# signal_processing_module.net
KiCad netlist of a schematic drawn in EAGLE
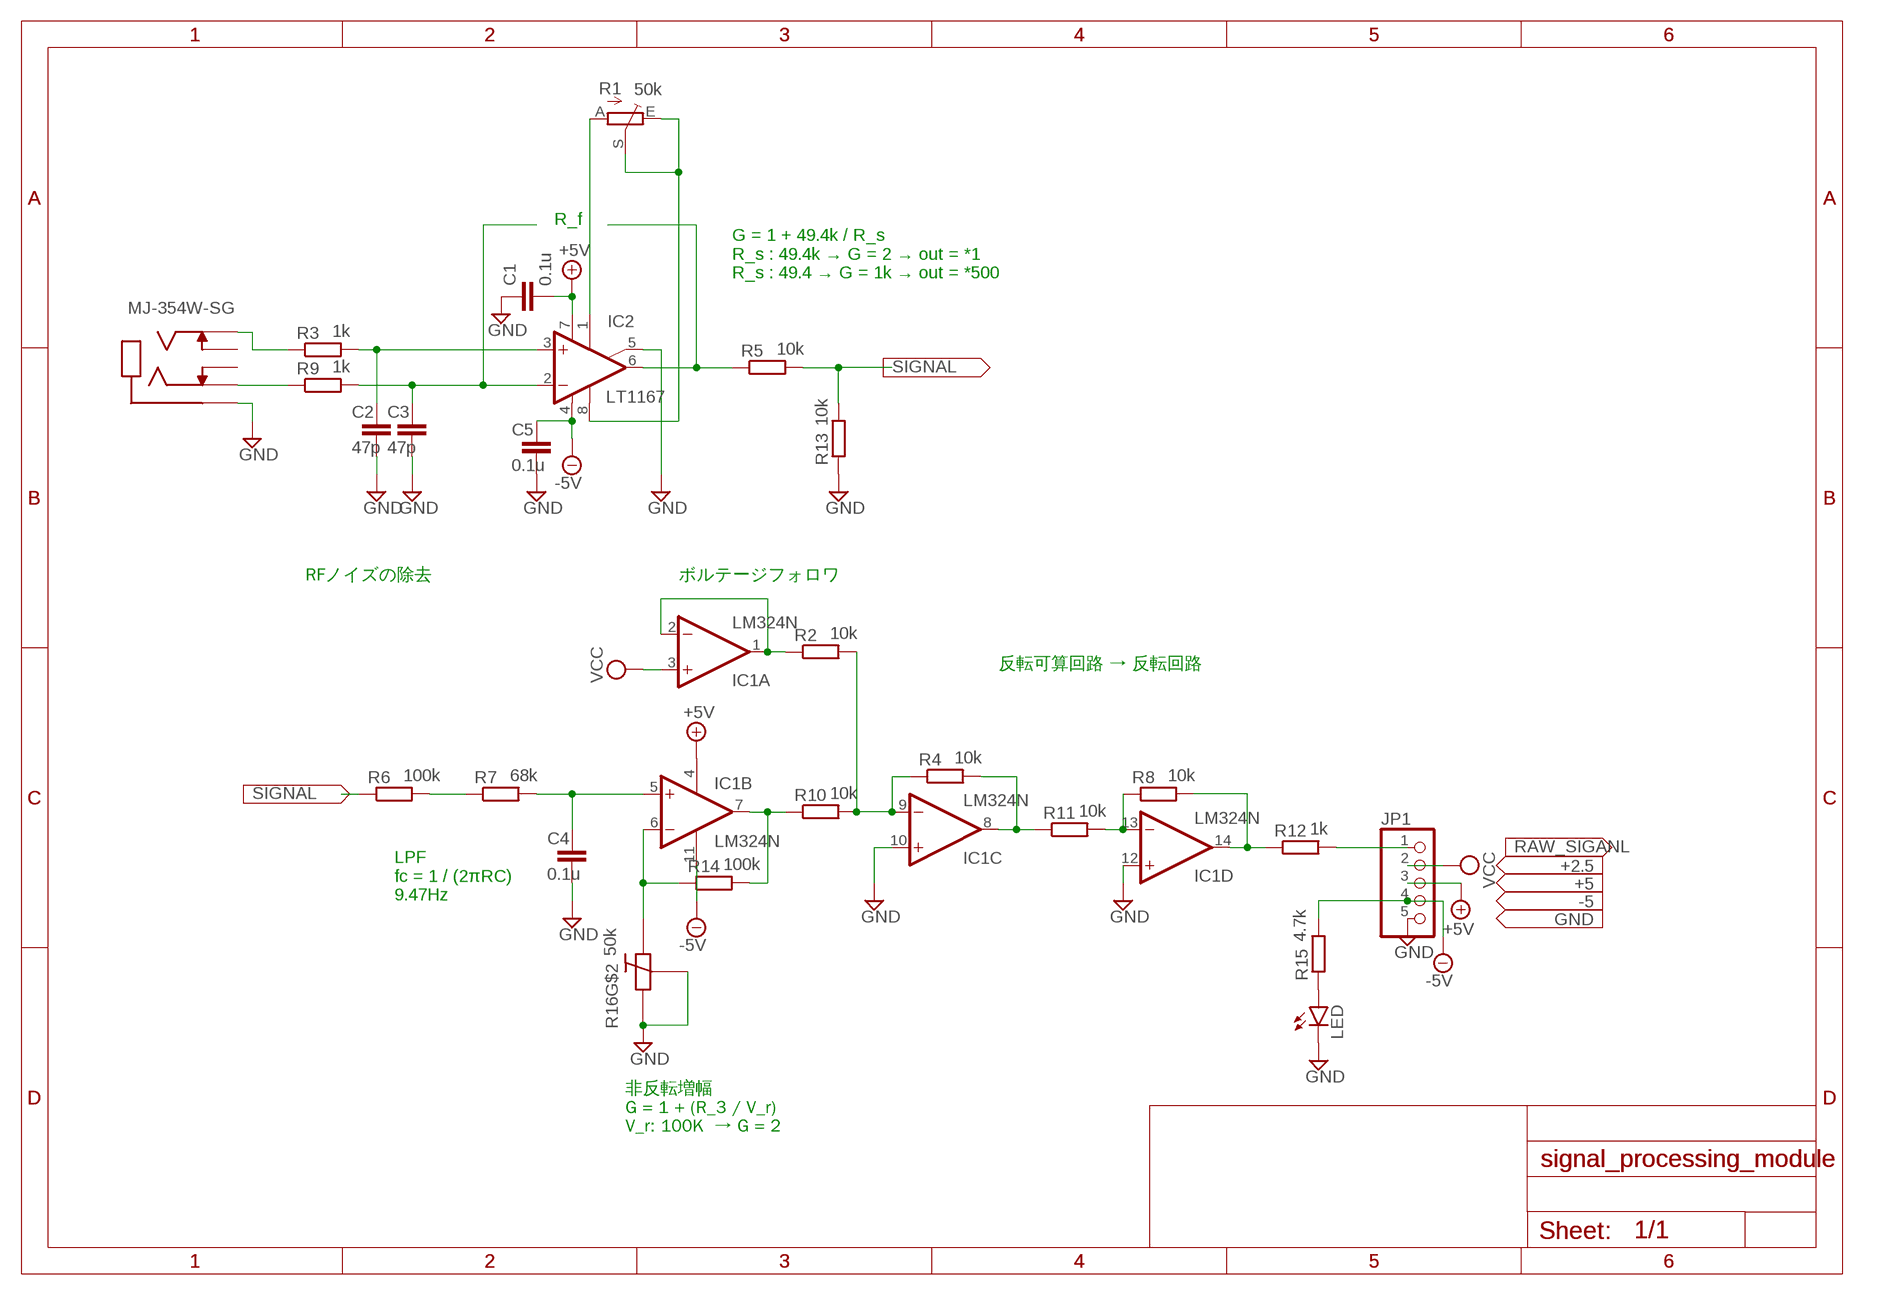
[diagram p0: schematic, sheet 1]

(export (version "E")
  (design (tool "Eeschema 10.0.6"))
  (components
    (comp (ref "C1")
      (value "0.1u")
      (footprint "eagle-import:C025-024X044")
      (libsource (lib "eagle-import") (part "C-EU025-024X044"))
    )
    (comp (ref "C2")
      (value "47p")
      (footprint "eagle-import:C025-024X044")
      (libsource (lib "eagle-import") (part "C-EU025-024X044"))
    )
    (comp (ref "C3")
      (value "47p")
      (footprint "eagle-import:C025-024X044")
      (libsource (lib "eagle-import") (part "C-EU025-024X044"))
    )
    (comp (ref "C4")
      (value "0.1u")
      (footprint "eagle-import:C025-024X044")
      (libsource (lib "eagle-import") (part "C-EU025-024X044"))
    )
    (comp (ref "C5")
      (value "0.1u")
      (footprint "eagle-import:C025-024X044")
      (libsource (lib "eagle-import") (part "C-EU025-024X044"))
    )
    (comp (ref "IC1")
      (value "LM324N")
      (footprint "eagle-import:DIL14")
      (libsource (lib "eagle-import") (part "LM324N"))
    )
    (comp (ref "IC2")
      (value "TL061P")
      (footprint "eagle-import:DIL08")
      (libsource (lib "eagle-import") (part "TL061P"))
    )
    (comp (ref "JP1")
      (value "PINHD-1X5")
      (footprint "eagle-import:1X05")
      (libsource (lib "eagle-import") (part "PINHD-1X5"))
    )
    (comp (ref "LED")
      (value "LED3MM")
      (footprint "eagle-import:LED3MM")
      (libsource (lib "eagle-import") (part "LED3MM"))
    )
    (comp (ref "R1")
      (value "50k")
      (footprint "eagle-import:RS3")
      (libsource (lib "eagle-import") (part "TRIM_EU-RS3"))
    )
    (comp (ref "R2")
      (value "10k")
      (footprint "eagle-import:0204_7")
      (libsource (lib "eagle-import") (part "R-EU_0204/7"))
    )
    (comp (ref "R3")
      (value "1k")
      (footprint "eagle-import:0204_7")
      (libsource (lib "eagle-import") (part "R-EU_0204/7"))
    )
    (comp (ref "R4")
      (value "10k")
      (footprint "eagle-import:0204_7")
      (libsource (lib "eagle-import") (part "R-EU_0204/7"))
    )
    (comp (ref "R5")
      (value "10k")
      (footprint "eagle-import:0204_7")
      (libsource (lib "eagle-import") (part "R-EU_0204/7"))
    )
    (comp (ref "R6")
      (value "100k")
      (footprint "eagle-import:0204_7")
      (libsource (lib "eagle-import") (part "R-EU_0204/7"))
    )
    (comp (ref "R7")
      (value "68k")
      (footprint "eagle-import:0204_7")
      (libsource (lib "eagle-import") (part "R-EU_0204/7"))
    )
    (comp (ref "R8")
      (value "10k")
      (footprint "eagle-import:0204_7")
      (libsource (lib "eagle-import") (part "R-EU_0204/7"))
    )
    (comp (ref "R9")
      (value "1k")
      (footprint "eagle-import:0204_7")
      (libsource (lib "eagle-import") (part "R-EU_0204/7"))
    )
    (comp (ref "R10")
      (value "10k")
      (footprint "eagle-import:0204_7")
      (libsource (lib "eagle-import") (part "R-EU_0204/7"))
    )
    (comp (ref "R11")
      (value "10k")
      (footprint "eagle-import:0204_7")
      (libsource (lib "eagle-import") (part "R-EU_0204/7"))
    )
    (comp (ref "R12")
      (value "1k")
      (footprint "eagle-import:0204_7")
      (libsource (lib "eagle-import") (part "R-EU_0204/7"))
    )
    (comp (ref "R13")
      (value "10k")
      (footprint "eagle-import:0204_7")
      (libsource (lib "eagle-import") (part "R-EU_0204/7"))
    )
    (comp (ref "R14")
      (value "100k")
      (footprint "eagle-import:0204_7")
      (libsource (lib "eagle-import") (part "R-EU_0204/7"))
    )
    (comp (ref "R15")
      (value "4.7k")
      (footprint "eagle-import:0204_7")
      (libsource (lib "eagle-import") (part "R-EU_0204/7"))
    )
    (comp (ref "R16")
      (value "50k")
      (footprint "eagle-import:2CH_VR")
      (libsource (lib "eagle-import") (part "VR_2CH"))
    )
    (comp (ref "U$1")
      (value "MJ-354W-SG-NEW")
      (footprint "eagle-import:MJ-354W-SG")
      (libsource (lib "eagle-import") (part "MJ-354W-SG-NEW"))
    )
  )
  (nets
    (net (code "1") (name "+5V") (class "Default")
      (node (ref "C1") (pin "2") (pinfunction "2_2") (pintype "passive"))
      (node (ref "IC1") (pin "4") (pinfunction "V+_4") (pintype "power_in"))
      (node (ref "IC2") (pin "7") (pinfunction "V+_7") (pintype "power_in"))
      (node (ref "JP1") (pin "3") (pinfunction "3_3") (pintype "passive"))
    )
    (net (code "2") (name "-5V") (class "Default")
      (node (ref "C5") (pin "1") (pinfunction "1_1") (pintype "passive"))
      (node (ref "IC1") (pin "11") (pinfunction "V-_11") (pintype "power_in"))
      (node (ref "IC2") (pin "4") (pinfunction "V-_4") (pintype "power_in"))
      (node (ref "JP1") (pin "4") (pinfunction "4_4") (pintype "passive"))
      (node (ref "R15") (pin "2") (pinfunction "2_2") (pintype "passive"))
    )
    (net (code "3") (name "GND") (class "Default")
      (node (ref "C1") (pin "1") (pinfunction "1_1") (pintype "passive"))
      (node (ref "C2") (pin "2") (pinfunction "2_2") (pintype "passive"))
      (node (ref "C3") (pin "2") (pinfunction "2_2") (pintype "passive"))
      (node (ref "C4") (pin "2") (pinfunction "2_2") (pintype "passive"))
      (node (ref "C5") (pin "2") (pinfunction "2_2") (pintype "passive"))
      (node (ref "IC1") (pin "10") (pinfunction "+IN_10") (pintype "input"))
      (node (ref "IC1") (pin "12") (pinfunction "+IN_12") (pintype "input"))
      (node (ref "IC2") (pin "5") (pinfunction "ON2_5") (pintype "passive"))
      (node (ref "JP1") (pin "5") (pinfunction "5_5") (pintype "passive"))
      (node (ref "LED") (pin "K") (pinfunction "C_K") (pintype "passive"))
      (node (ref "R13") (pin "1") (pinfunction "1_1") (pintype "passive"))
      (node (ref "R16") (pin "P$4") (pinfunction "P$1_P$4") (pintype "bidirectional"))
      (node (ref "R16") (pin "P$5") (pinfunction "P$2_P$5") (pintype "bidirectional"))
      (node (ref "U$1") (pin "P$1") (pinfunction "P$1_P$1") (pintype "bidirectional"))
    )
    (net (code "4") (name "Net-(IC1A--IN)") (class "Default")
      (node (ref "IC1") (pin "1") (pinfunction "OUT_1") (pintype "output"))
      (node (ref "IC1") (pin "2") (pinfunction "-IN_2") (pintype "input"))
      (node (ref "R2") (pin "1") (pinfunction "1_1") (pintype "passive"))
    )
    (net (code "5") (name "Net-(IC1B-+IN)") (class "Default")
      (node (ref "C4") (pin "1") (pinfunction "1_1") (pintype "passive"))
      (node (ref "IC1") (pin "5") (pinfunction "+IN_5") (pintype "input"))
      (node (ref "R7") (pin "2") (pinfunction "2_2") (pintype "passive"))
    )
    (net (code "6") (name "Net-(IC1B--IN)") (class "Default")
      (node (ref "IC1") (pin "6") (pinfunction "-IN_6") (pintype "input"))
      (node (ref "R14") (pin "1") (pinfunction "1_1") (pintype "passive"))
      (node (ref "R16") (pin "P$6") (pinfunction "P$3_P$6") (pintype "bidirectional"))
    )
    (net (code "7") (name "Net-(IC1B-OUT)") (class "Default")
      (node (ref "IC1") (pin "7") (pinfunction "OUT_7") (pintype "output"))
      (node (ref "R10") (pin "1") (pinfunction "1_1") (pintype "passive"))
      (node (ref "R14") (pin "2") (pinfunction "2_2") (pintype "passive"))
    )
    (net (code "8") (name "Net-(IC1C--IN)") (class "Default")
      (node (ref "IC1") (pin "9") (pinfunction "-IN_9") (pintype "input"))
      (node (ref "R10") (pin "2") (pinfunction "2_2") (pintype "passive"))
      (node (ref "R2") (pin "2") (pinfunction "2_2") (pintype "passive"))
      (node (ref "R4") (pin "1") (pinfunction "1_1") (pintype "passive"))
    )
    (net (code "9") (name "Net-(IC1C-OUT)") (class "Default")
      (node (ref "IC1") (pin "8") (pinfunction "OUT_8") (pintype "output"))
      (node (ref "R11") (pin "1") (pinfunction "1_1") (pintype "passive"))
      (node (ref "R4") (pin "2") (pinfunction "2_2") (pintype "passive"))
    )
    (net (code "10") (name "Net-(IC1D--IN)") (class "Default")
      (node (ref "IC1") (pin "13") (pinfunction "-IN_13") (pintype "input"))
      (node (ref "R11") (pin "2") (pinfunction "2_2") (pintype "passive"))
      (node (ref "R8") (pin "1") (pinfunction "1_1") (pintype "passive"))
    )
    (net (code "11") (name "Net-(IC1D-OUT)") (class "Default")
      (node (ref "IC1") (pin "14") (pinfunction "OUT_14") (pintype "output"))
      (node (ref "R12") (pin "1") (pinfunction "1_1") (pintype "passive"))
      (node (ref "R8") (pin "2") (pinfunction "2_2") (pintype "passive"))
    )
    (net (code "12") (name "Net-(IC2-+IN)") (class "Default")
      (node (ref "C2") (pin "1") (pinfunction "1_1") (pintype "passive"))
      (node (ref "IC2") (pin "3") (pinfunction "+IN_3") (pintype "input"))
      (node (ref "R3") (pin "2") (pinfunction "2_2") (pintype "passive"))
    )
    (net (code "13") (name "Net-(IC2--IN)") (class "Default")
      (node (ref "C3") (pin "1") (pinfunction "1_1") (pintype "passive"))
      (node (ref "IC2") (pin "2") (pinfunction "-IN_2") (pintype "input"))
      (node (ref "R9") (pin "2") (pinfunction "2_2") (pintype "passive"))
    )
    (net (code "14") (name "Net-(IC2-ON1)") (class "Default")
      (node (ref "IC2") (pin "1") (pinfunction "ON1_1") (pintype "passive"))
      (node (ref "R1") (pin "A") (pinfunction "A_A") (pintype "passive"))
    )
    (net (code "15") (name "Net-(IC2-OPT)") (class "Default")
      (node (ref "IC2") (pin "8") (pinfunction "OPT_8") (pintype "passive"))
      (node (ref "R1") (pin "E") (pinfunction "E_E") (pintype "passive"))
      (node (ref "R1") (pin "S") (pinfunction "S_S") (pintype "passive"))
    )
    (net (code "16") (name "Net-(IC2-OUT)") (class "Default")
      (node (ref "IC2") (pin "6") (pinfunction "OUT_6") (pintype "output"))
      (node (ref "R5") (pin "1") (pinfunction "1_1") (pintype "passive"))
    )
    (net (code "17") (name "Net-(JP1-Pad1)") (class "Default")
      (node (ref "JP1") (pin "1") (pinfunction "1_1") (pintype "passive"))
      (node (ref "R12") (pin "2") (pinfunction "2_2") (pintype "passive"))
    )
    (net (code "18") (name "Net-(LED-PadA)") (class "Default")
      (node (ref "LED") (pin "A") (pinfunction "A_A") (pintype "passive"))
      (node (ref "R15") (pin "1") (pinfunction "1_1") (pintype "passive"))
    )
    (net (code "19") (name "Net-(R3-Pad1)") (class "Default")
      (node (ref "R3") (pin "1") (pinfunction "1_1") (pintype "passive"))
      (node (ref "U$1") (pin "P$4") (pinfunction "P$4_P$4") (pintype "bidirectional"))
    )
    (net (code "20") (name "Net-(R6-Pad2)") (class "Default")
      (node (ref "R6") (pin "2") (pinfunction "2_2") (pintype "passive"))
      (node (ref "R7") (pin "1") (pinfunction "1_1") (pintype "passive"))
    )
    (net (code "21") (name "Net-(R9-Pad1)") (class "Default")
      (node (ref "R9") (pin "1") (pinfunction "1_1") (pintype "passive"))
      (node (ref "U$1") (pin "P$2") (pinfunction "P$2_P$2") (pintype "bidirectional"))
    )
    (net (code "22") (name "Net-(R13-Pad2)") (class "Default")
      (node (ref "R13") (pin "2") (pinfunction "2_2") (pintype "passive"))
      (node (ref "R5") (pin "2") (pinfunction "2_2") (pintype "passive"))
    )
    (net (code "23") (name "VCC") (class "Default")
      (node (ref "IC1") (pin "3") (pinfunction "+IN_3") (pintype "input"))
      (node (ref "JP1") (pin "2") (pinfunction "2_2") (pintype "passive"))
    )
    (net (code "24") (name "unconnected-(R6-Pad1)") (class "Default")
      (node (ref "R6") (pin "1") (pinfunction "1_1") (pintype "passive"))
    )
    (net (code "25") (name "unconnected-(U$1-PadP$3)") (class "Default")
      (node (ref "U$1") (pin "P$3") (pinfunction "P$3_P$3") (pintype "bidirectional"))
    )
    (net (code "26") (name "unconnected-(U$1-PadP$5)") (class "Default")
      (node (ref "U$1") (pin "P$5") (pinfunction "P$5_P$5") (pintype "bidirectional"))
    )
  )
)
